# 555_Timer.net
KiCad netlist of a schematic drawn in EAGLE
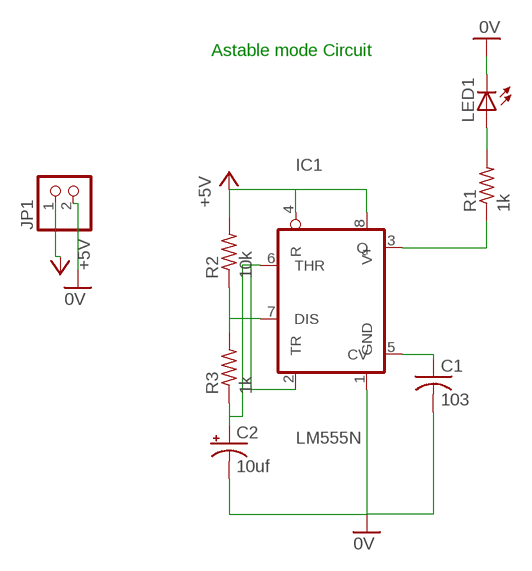
[diagram p0: schematic, sheet 1]

(export (version "E")
  (design (tool "Eeschema 10.0.6"))
  (components
    (comp (ref "C1")
      (value "103")
      (footprint "eagle-import:C025-024X044")
      (libsource (lib "eagle-import") (part "C-US025-024X044"))
    )
    (comp (ref "C2")
      (value "10uf")
      (footprint "eagle-import:E2-5")
      (libsource (lib "eagle-import") (part "CPOL-USE2-5"))
    )
    (comp (ref "IC1")
      (value "LM555N")
      (footprint "eagle-import:DIL08")
      (libsource (lib "eagle-import") (part "555NLM"))
    )
    (comp (ref "JP1")
      (value "PINHD-1X2")
      (footprint "eagle-import:1X02")
      (libsource (lib "eagle-import") (part "PINHD-1X2"))
    )
    (comp (ref "LED1")
      (value "LED5MM")
      (footprint "eagle-import:LED5MM")
      (libsource (lib "eagle-import") (part "LED5MM"))
    )
    (comp (ref "R1")
      (value "1k")
      (footprint "eagle-import:0207_10")
      (libsource (lib "eagle-import") (part "R-US_0207/10"))
    )
    (comp (ref "R2")
      (value "10k")
      (footprint "eagle-import:0207_10")
      (libsource (lib "eagle-import") (part "R-US_0207/10"))
    )
    (comp (ref "R3")
      (value "1k")
      (footprint "eagle-import:0207_10")
      (libsource (lib "eagle-import") (part "R-US_0207/10"))
    )
  )
  (nets
    (net (code "1") (name "+5V") (class "Default")
      (node (ref "IC1") (pin "4") (pinfunction "R_4") (pintype "input"))
      (node (ref "IC1") (pin "8") (pinfunction "V+_8") (pintype "power_in"))
      (node (ref "JP1") (pin "1") (pinfunction "1_1") (pintype "passive"))
      (node (ref "R2") (pin "2") (pinfunction "2_2") (pintype "passive"))
    )
    (net (code "2") (name "0V") (class "Default")
      (node (ref "C1") (pin "2") (pinfunction "2_2") (pintype "passive"))
      (node (ref "C2") (pin "-") (pinfunction "-_-") (pintype "passive"))
      (node (ref "IC1") (pin "1") (pinfunction "GND_1") (pintype "power_in"))
      (node (ref "JP1") (pin "2") (pinfunction "2_2") (pintype "passive"))
      (node (ref "LED1") (pin "K") (pinfunction "C_K") (pintype "passive"))
    )
    (net (code "3") (name "Net-(IC1-CV)") (class "Default")
      (node (ref "C1") (pin "1") (pinfunction "1_1") (pintype "passive"))
      (node (ref "IC1") (pin "5") (pinfunction "CV_5") (pintype "input"))
    )
    (net (code "4") (name "Net-(IC1-DIS)") (class "Default")
      (node (ref "IC1") (pin "7") (pinfunction "DIS_7") (pintype "input"))
      (node (ref "R2") (pin "1") (pinfunction "1_1") (pintype "passive"))
      (node (ref "R3") (pin "2") (pinfunction "2_2") (pintype "passive"))
    )
    (net (code "5") (name "Net-(IC1-Q)") (class "Default")
      (node (ref "IC1") (pin "3") (pinfunction "Q_3") (pintype "output"))
      (node (ref "R1") (pin "1") (pinfunction "1_1") (pintype "passive"))
    )
    (net (code "6") (name "Net-(IC1-THR)") (class "Default")
      (node (ref "C2") (pin "+") (pinfunction "+_+") (pintype "passive"))
      (node (ref "IC1") (pin "2") (pinfunction "TR_2") (pintype "input"))
      (node (ref "IC1") (pin "6") (pinfunction "THR_6") (pintype "input"))
      (node (ref "R3") (pin "1") (pinfunction "1_1") (pintype "passive"))
    )
    (net (code "7") (name "Net-(LED1-PadA)") (class "Default")
      (node (ref "LED1") (pin "A") (pinfunction "A_A") (pintype "passive"))
      (node (ref "R1") (pin "2") (pinfunction "2_2") (pintype "passive"))
    )
  )
)
